# Button_pannel.net
KiCad netlist of a schematic drawn in EAGLE
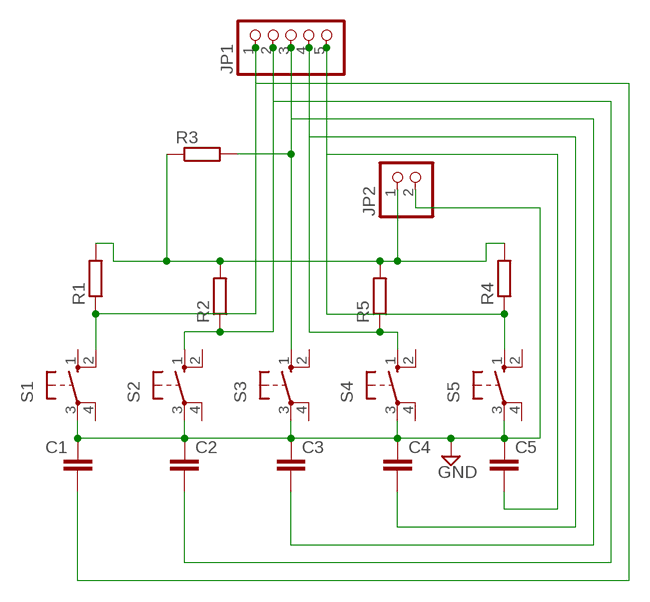
[diagram p0: schematic, sheet 1]

(export (version "E")
  (design (tool "Eeschema 10.0.6"))
  (components
    (comp (ref "C1")
      (value "C-EU025-025X050")
      (footprint "eagle-import:C025-025X050")
      (libsource (lib "eagle-import") (part "C-EU025-025X050"))
    )
    (comp (ref "C2")
      (value "C-EU025-025X050")
      (footprint "eagle-import:C025-025X050")
      (libsource (lib "eagle-import") (part "C-EU025-025X050"))
    )
    (comp (ref "C3")
      (value "C-EU025-025X050")
      (footprint "eagle-import:C025-025X050")
      (libsource (lib "eagle-import") (part "C-EU025-025X050"))
    )
    (comp (ref "C4")
      (value "C-EU025-025X050")
      (footprint "eagle-import:C025-025X050")
      (libsource (lib "eagle-import") (part "C-EU025-025X050"))
    )
    (comp (ref "C5")
      (value "C-EU025-025X050")
      (footprint "eagle-import:C025-025X050")
      (libsource (lib "eagle-import") (part "C-EU025-025X050"))
    )
    (comp (ref "JP1")
      (value "PINHD-1X5")
      (footprint "eagle-import:1X05")
      (libsource (lib "eagle-import") (part "PINHD-1X5"))
    )
    (comp (ref "JP2")
      (value "PINHD-1X2")
      (footprint "eagle-import:1X02")
      (libsource (lib "eagle-import") (part "PINHD-1X2"))
    )
    (comp (ref "R1")
      (value "R-EU_0204/7")
      (footprint "eagle-import:0204_7")
      (libsource (lib "eagle-import") (part "R-EU_0204/7"))
    )
    (comp (ref "R2")
      (value "R-EU_0204/7")
      (footprint "eagle-import:0204_7")
      (libsource (lib "eagle-import") (part "R-EU_0204/7"))
    )
    (comp (ref "R3")
      (value "R-EU_0204/7")
      (footprint "eagle-import:0204_7")
      (libsource (lib "eagle-import") (part "R-EU_0204/7"))
    )
    (comp (ref "R4")
      (value "R-EU_0204/7")
      (footprint "eagle-import:0204_7")
      (libsource (lib "eagle-import") (part "R-EU_0204/7"))
    )
    (comp (ref "R5")
      (value "R-EU_0204/7")
      (footprint "eagle-import:0204_7")
      (libsource (lib "eagle-import") (part "R-EU_0204/7"))
    )
    (comp (ref "S1")
      (value "40-XX")
      (footprint "eagle-import:B3F-40XX")
      (libsource (lib "eagle-import") (part "40-XX"))
    )
    (comp (ref "S2")
      (value "40-XX")
      (footprint "eagle-import:B3F-40XX")
      (libsource (lib "eagle-import") (part "40-XX"))
    )
    (comp (ref "S3")
      (value "40-XX")
      (footprint "eagle-import:B3F-40XX")
      (libsource (lib "eagle-import") (part "40-XX"))
    )
    (comp (ref "S4")
      (value "40-XX")
      (footprint "eagle-import:B3F-40XX")
      (libsource (lib "eagle-import") (part "40-XX"))
    )
    (comp (ref "S5")
      (value "40-XX")
      (footprint "eagle-import:B3F-40XX")
      (libsource (lib "eagle-import") (part "40-XX"))
    )
  )
  (nets
    (net (code "1") (name "GND") (class "Default")
      (node (ref "C1") (pin "1") (pinfunction "1_1") (pintype "passive"))
      (node (ref "C2") (pin "1") (pinfunction "1_1") (pintype "passive"))
      (node (ref "C3") (pin "1") (pinfunction "1_1") (pintype "passive"))
      (node (ref "C4") (pin "1") (pinfunction "1_1") (pintype "passive"))
      (node (ref "C5") (pin "1") (pinfunction "1_1") (pintype "passive"))
      (node (ref "JP2") (pin "2") (pinfunction "2_2") (pintype "passive"))
      (node (ref "S1") (pin "3") (pinfunction "P_3") (pintype "passive"))
      (node (ref "S2") (pin "3") (pinfunction "P_3") (pintype "passive"))
      (node (ref "S3") (pin "3") (pinfunction "P_3") (pintype "passive"))
      (node (ref "S4") (pin "3") (pinfunction "P_3") (pintype "passive"))
      (node (ref "S5") (pin "3") (pinfunction "P_3") (pintype "passive"))
    )
    (net (code "2") (name "Net-(JP2-Pad1)") (class "Default")
      (node (ref "JP2") (pin "1") (pinfunction "1_1") (pintype "passive"))
      (node (ref "R1") (pin "2") (pinfunction "2_2") (pintype "passive"))
      (node (ref "R2") (pin "2") (pinfunction "2_2") (pintype "passive"))
      (node (ref "R3") (pin "1") (pinfunction "1_1") (pintype "passive"))
      (node (ref "R4") (pin "2") (pinfunction "2_2") (pintype "passive"))
      (node (ref "R5") (pin "2") (pinfunction "2_2") (pintype "passive"))
    )
    (net (code "3") (name "Net-(S1-S1)") (class "Default")
      (node (ref "C1") (pin "2") (pinfunction "2_2") (pintype "passive"))
      (node (ref "JP1") (pin "1") (pinfunction "1_1") (pintype "passive"))
      (node (ref "R1") (pin "1") (pinfunction "1_1") (pintype "passive"))
      (node (ref "S1") (pin "2") (pinfunction "S1_2") (pintype "passive"))
    )
    (net (code "4") (name "Net-(S2-S)") (class "Default")
      (node (ref "C2") (pin "2") (pinfunction "2_2") (pintype "passive"))
      (node (ref "JP1") (pin "2") (pinfunction "2_2") (pintype "passive"))
      (node (ref "R2") (pin "1") (pinfunction "1_1") (pintype "passive"))
      (node (ref "S2") (pin "1") (pinfunction "S_1") (pintype "passive"))
    )
    (net (code "5") (name "Net-(S3-S)") (class "Default")
      (node (ref "C3") (pin "2") (pinfunction "2_2") (pintype "passive"))
      (node (ref "JP1") (pin "3") (pinfunction "3_3") (pintype "passive"))
      (node (ref "R3") (pin "2") (pinfunction "2_2") (pintype "passive"))
      (node (ref "S3") (pin "1") (pinfunction "S_1") (pintype "passive"))
    )
    (net (code "6") (name "Net-(S4-S)") (class "Default")
      (node (ref "C4") (pin "2") (pinfunction "2_2") (pintype "passive"))
      (node (ref "JP1") (pin "4") (pinfunction "4_4") (pintype "passive"))
      (node (ref "R5") (pin "1") (pinfunction "1_1") (pintype "passive"))
      (node (ref "S4") (pin "1") (pinfunction "S_1") (pintype "passive"))
    )
    (net (code "7") (name "Net-(S5-S)") (class "Default")
      (node (ref "C5") (pin "2") (pinfunction "2_2") (pintype "passive"))
      (node (ref "JP1") (pin "5") (pinfunction "5_5") (pintype "passive"))
      (node (ref "R4") (pin "1") (pinfunction "1_1") (pintype "passive"))
      (node (ref "S5") (pin "1") (pinfunction "S_1") (pintype "passive"))
    )
    (net (code "8") (name "unconnected-(S1-P1-Pad4)") (class "Default")
      (node (ref "S1") (pin "4") (pinfunction "P1_4") (pintype "passive"))
    )
    (net (code "9") (name "unconnected-(S1-S-Pad1)") (class "Default")
      (node (ref "S1") (pin "1") (pinfunction "S_1") (pintype "passive"))
    )
    (net (code "10") (name "unconnected-(S2-P1-Pad4)") (class "Default")
      (node (ref "S2") (pin "4") (pinfunction "P1_4") (pintype "passive"))
    )
    (net (code "11") (name "unconnected-(S2-S1-Pad2)") (class "Default")
      (node (ref "S2") (pin "2") (pinfunction "S1_2") (pintype "passive"))
    )
    (net (code "12") (name "unconnected-(S3-P1-Pad4)") (class "Default")
      (node (ref "S3") (pin "4") (pinfunction "P1_4") (pintype "passive"))
    )
    (net (code "13") (name "unconnected-(S3-S1-Pad2)") (class "Default")
      (node (ref "S3") (pin "2") (pinfunction "S1_2") (pintype "passive"))
    )
    (net (code "14") (name "unconnected-(S4-P1-Pad4)") (class "Default")
      (node (ref "S4") (pin "4") (pinfunction "P1_4") (pintype "passive"))
    )
    (net (code "15") (name "unconnected-(S4-S1-Pad2)") (class "Default")
      (node (ref "S4") (pin "2") (pinfunction "S1_2") (pintype "passive"))
    )
    (net (code "16") (name "unconnected-(S5-P1-Pad4)") (class "Default")
      (node (ref "S5") (pin "4") (pinfunction "P1_4") (pintype "passive"))
    )
    (net (code "17") (name "unconnected-(S5-S1-Pad2)") (class "Default")
      (node (ref "S5") (pin "2") (pinfunction "S1_2") (pintype "passive"))
    )
  )
)
